# rc-driver-dual-rev-b.net
KiCad netlist of a schematic drawn in EAGLE
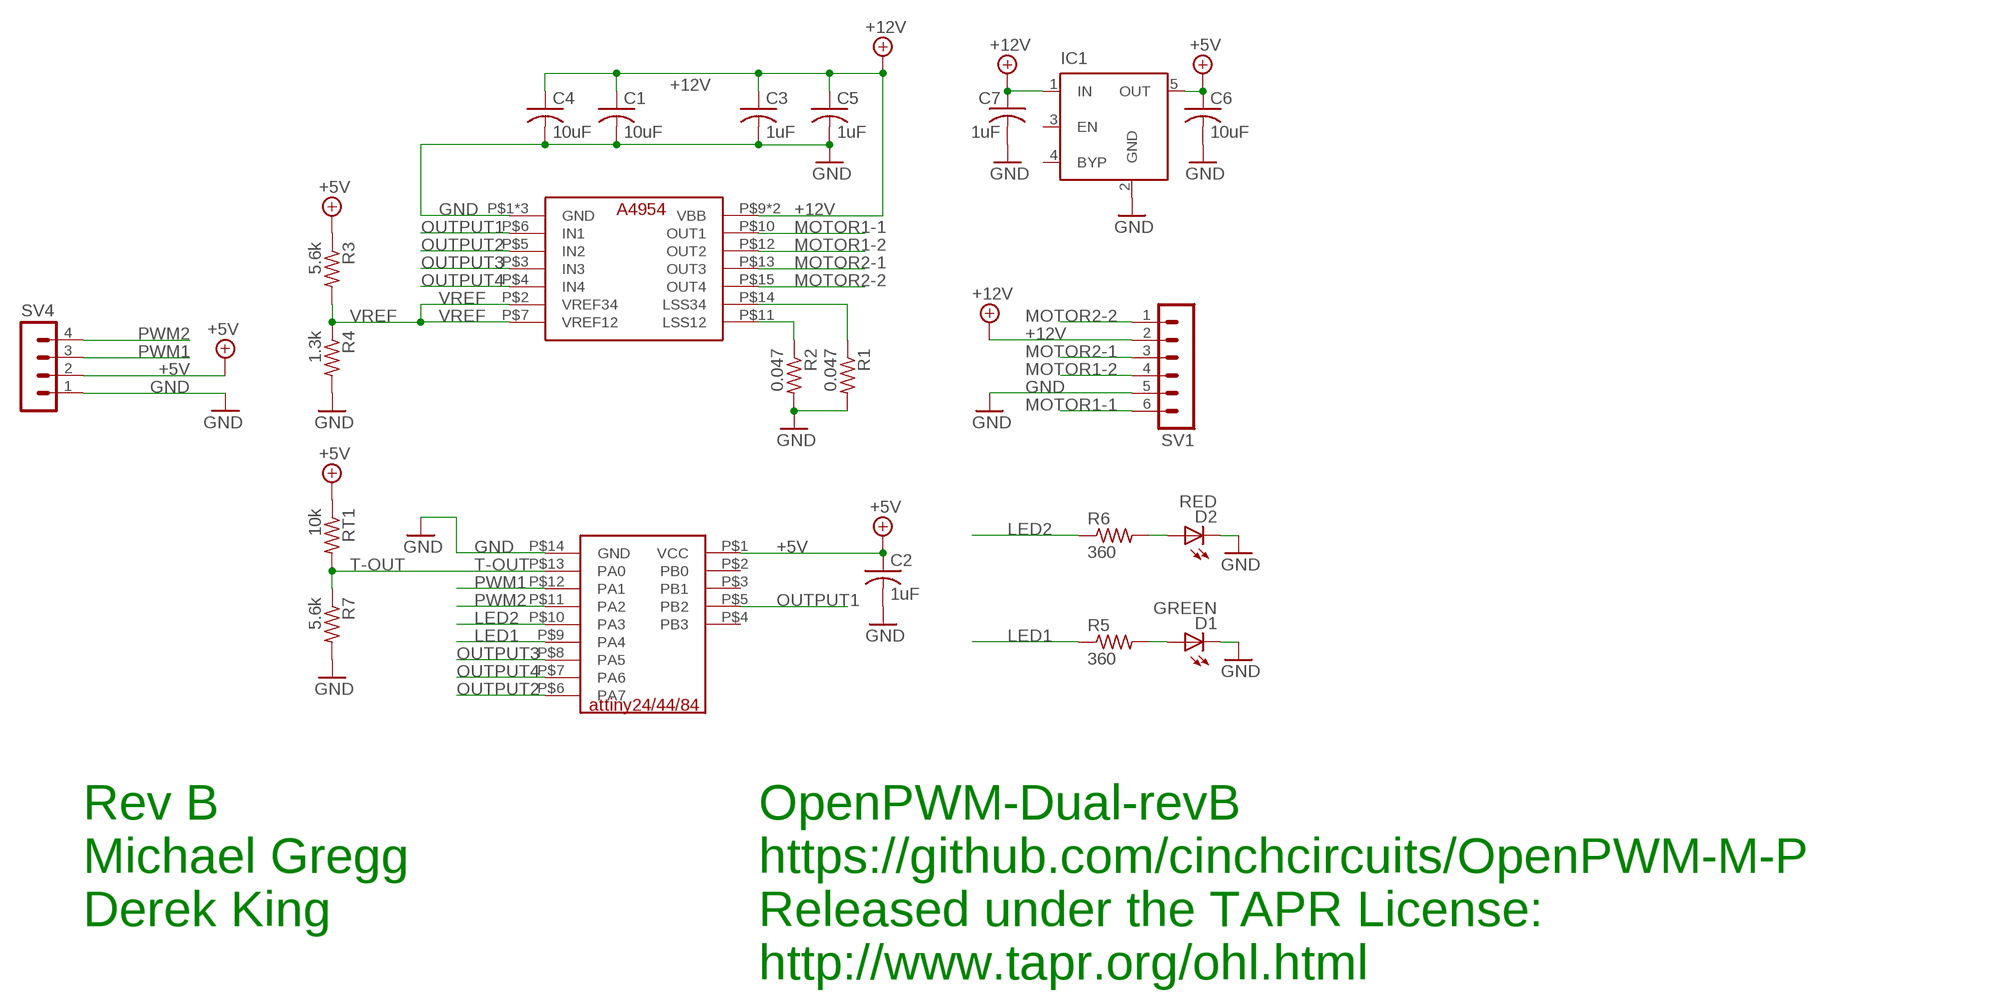
[diagram p0: schematic, sheet 1]

(export (version "E")
  (design (tool "Eeschema 10.0.6"))
  (components
    (comp (ref "C1")
      (value "10uF")
      (footprint "eagle-import:C1206")
      (libsource (lib "eagle-import") (part "C-USC1206"))
    )
    (comp (ref "C2")
      (value "1uF")
      (footprint "eagle-import:C0603")
      (libsource (lib "eagle-import") (part "C-USC0603"))
    )
    (comp (ref "C3")
      (value "1uF")
      (footprint "eagle-import:C0603")
      (libsource (lib "eagle-import") (part "C-USC0603"))
    )
    (comp (ref "C4")
      (value "10uF")
      (footprint "eagle-import:C1206")
      (libsource (lib "eagle-import") (part "C-USC1206"))
    )
    (comp (ref "C5")
      (value "1uF")
      (footprint "eagle-import:C0603")
      (libsource (lib "eagle-import") (part "C-USC0603"))
    )
    (comp (ref "C6")
      (value "10uF")
      (footprint "eagle-import:C1206")
      (libsource (lib "eagle-import") (part "C-USC1206"))
    )
    (comp (ref "C7")
      (value "1uF")
      (footprint "eagle-import:C0603")
      (libsource (lib "eagle-import") (part "C-USC0603"))
    )
    (comp (ref "D1")
      (value "GREEN")
      (footprint "eagle-import:CHIPLED_0603")
      (libsource (lib "eagle-import") (part "LEDCHIPLED_0603"))
    )
    (comp (ref "D2")
      (value "RED")
      (footprint "eagle-import:CHIPLED_0603")
      (libsource (lib "eagle-import") (part "LEDCHIPLED_0603"))
    )
    (comp (ref "IC1")
      (value "MIC5219XX")
      (footprint "eagle-import:SOT23-5")
      (fields (field (name "MF") "Texas Instruments") (field (name "MPN") "TPS70950"))
      (libsource (lib "eagle-import") (part "MIC5219XX"))
    )
    (comp (ref "R1")
      (value "0.047")
      (footprint "eagle-import:R0805")
      (libsource (lib "eagle-import") (part "R-US_R0805"))
    )
    (comp (ref "R2")
      (value "0.047")
      (footprint "eagle-import:R0805")
      (libsource (lib "eagle-import") (part "R-US_R0805"))
    )
    (comp (ref "R3")
      (value "5.6k")
      (footprint "eagle-import:R0603")
      (libsource (lib "eagle-import") (part "R-US_R0603"))
    )
    (comp (ref "R4")
      (value "1.3k")
      (footprint "eagle-import:R0603")
      (libsource (lib "eagle-import") (part "R-US_R0603"))
    )
    (comp (ref "R5")
      (value "360")
      (footprint "eagle-import:R0603")
      (libsource (lib "eagle-import") (part "R-US_R0603"))
    )
    (comp (ref "R6")
      (value "360")
      (footprint "eagle-import:R0603")
      (libsource (lib "eagle-import") (part "R-US_R0603"))
    )
    (comp (ref "R7")
      (value "5.6k")
      (footprint "eagle-import:R0603")
      (libsource (lib "eagle-import") (part "R-US_R0603"))
    )
    (comp (ref "RT1")
      (value "10k")
      (footprint "eagle-import:R0603")
      (libsource (lib "eagle-import") (part "R-US_R0603"))
    )
    (comp (ref "SV1")
      (value "MA06-1")
      (footprint "eagle-import:MA06-1")
      (libsource (lib "eagle-import") (part "MA06-1"))
    )
    (comp (ref "SV4")
      (value "MA04-1")
      (footprint "eagle-import:MA04-1")
      (libsource (lib "eagle-import") (part "MA04-1"))
    )
    (comp (ref "U$1")
      (value "ATTINY24A")
      (footprint "eagle-import:SOIC-14-WIDE")
      (fields (field (name "MF") "Atmel") (field (name "MPN") "ATTINY24A-SSUR"))
      (libsource (lib "eagle-import") (part "ATTINY24A"))
    )
    (comp (ref "U$2")
      (value "A4954-DUAL-HBRIDGE")
      (footprint "eagle-import:TSSOP-16-LP")
      (fields (field (name "MF") "Allegro") (field (name "MPN") "A4954"))
      (libsource (lib "eagle-import") (part "A4954-DUAL-HBRIDGE"))
    )
  )
  (nets
    (net (code "1") (name "+5V") (class "Default")
      (node (ref "C2") (pin "1") (pinfunction "1_1") (pintype "passive"))
      (node (ref "C6") (pin "1") (pinfunction "1_1") (pintype "passive"))
      (node (ref "IC1") (pin "5") (pinfunction "OUT_5") (pintype "output"))
      (node (ref "R3") (pin "1") (pinfunction "1_1") (pintype "passive"))
      (node (ref "RT1") (pin "1") (pinfunction "1_1") (pintype "passive"))
      (node (ref "SV4") (pin "2") (pinfunction "2_2") (pintype "passive"))
      (node (ref "U$1") (pin "P$1") (pinfunction "VCC_P$1") (pintype "bidirectional"))
    )
    (net (code "2") (name "+12V") (class "Default")
      (node (ref "C1") (pin "1") (pinfunction "1_1") (pintype "passive"))
      (node (ref "C3") (pin "1") (pinfunction "1_1") (pintype "passive"))
      (node (ref "C4") (pin "1") (pinfunction "1_1") (pintype "passive"))
      (node (ref "C5") (pin "1") (pinfunction "1_1") (pintype "passive"))
      (node (ref "C7") (pin "1") (pinfunction "1_1") (pintype "passive"))
      (node (ref "IC1") (pin "1") (pinfunction "IN_1") (pintype "input"))
      (node (ref "SV1") (pin "2") (pinfunction "2_2") (pintype "passive"))
      (node (ref "U$2") (pin "P$16") (pinfunction "VBB_P$16") (pintype "bidirectional"))
      (node (ref "U$2") (pin "P$9") (pinfunction "VBB_P$9") (pintype "bidirectional"))
    )
    (net (code "3") (name "/LED1") (class "Default")
      (node (ref "R5") (pin "1") (pinfunction "1_1") (pintype "passive"))
      (node (ref "U$1") (pin "P$9") (pinfunction "PA4_P$9") (pintype "bidirectional"))
    )
    (net (code "4") (name "/LED2") (class "Default")
      (node (ref "R6") (pin "1") (pinfunction "1_1") (pintype "passive"))
      (node (ref "U$1") (pin "P$10") (pinfunction "PA3_P$10") (pintype "bidirectional"))
    )
    (net (code "5") (name "/MOTOR1-1") (class "Default")
      (node (ref "SV1") (pin "6") (pinfunction "6_6") (pintype "passive"))
      (node (ref "U$2") (pin "P$10") (pinfunction "OUT1_P$10") (pintype "bidirectional"))
    )
    (net (code "6") (name "/MOTOR1-2") (class "Default")
      (node (ref "SV1") (pin "4") (pinfunction "4_4") (pintype "passive"))
      (node (ref "U$2") (pin "P$12") (pinfunction "OUT2_P$12") (pintype "bidirectional"))
    )
    (net (code "7") (name "/MOTOR2-1") (class "Default")
      (node (ref "SV1") (pin "3") (pinfunction "3_3") (pintype "passive"))
      (node (ref "U$2") (pin "P$13") (pinfunction "OUT3_P$13") (pintype "bidirectional"))
    )
    (net (code "8") (name "/MOTOR2-2") (class "Default")
      (node (ref "SV1") (pin "1") (pinfunction "1_1") (pintype "passive"))
      (node (ref "U$2") (pin "P$15") (pinfunction "OUT4_P$15") (pintype "bidirectional"))
    )
    (net (code "9") (name "/OUTPUT1") (class "Default")
      (node (ref "U$1") (pin "P$5") (pinfunction "PB2_P$5") (pintype "bidirectional"))
      (node (ref "U$2") (pin "P$6") (pinfunction "IN1_P$6") (pintype "bidirectional"))
    )
    (net (code "10") (name "/OUTPUT2") (class "Default")
      (node (ref "U$1") (pin "P$6") (pinfunction "PA7_P$6") (pintype "bidirectional"))
      (node (ref "U$2") (pin "P$5") (pinfunction "IN2_P$5") (pintype "bidirectional"))
    )
    (net (code "11") (name "/OUTPUT3") (class "Default")
      (node (ref "U$1") (pin "P$8") (pinfunction "PA5_P$8") (pintype "bidirectional"))
      (node (ref "U$2") (pin "P$3") (pinfunction "IN3_P$3") (pintype "bidirectional"))
    )
    (net (code "12") (name "/OUTPUT4") (class "Default")
      (node (ref "U$1") (pin "P$7") (pinfunction "PA6_P$7") (pintype "bidirectional"))
      (node (ref "U$2") (pin "P$4") (pinfunction "IN4_P$4") (pintype "bidirectional"))
    )
    (net (code "13") (name "/PWM1") (class "Default")
      (node (ref "SV4") (pin "3") (pinfunction "3_3") (pintype "passive"))
      (node (ref "U$1") (pin "P$12") (pinfunction "PA1_P$12") (pintype "bidirectional"))
    )
    (net (code "14") (name "/PWM2") (class "Default")
      (node (ref "SV4") (pin "4") (pinfunction "4_4") (pintype "passive"))
      (node (ref "U$1") (pin "P$11") (pinfunction "PA2_P$11") (pintype "bidirectional"))
    )
    (net (code "15") (name "/T-OUT") (class "Default")
      (node (ref "R7") (pin "1") (pinfunction "1_1") (pintype "passive"))
      (node (ref "RT1") (pin "2") (pinfunction "2_2") (pintype "passive"))
      (node (ref "U$1") (pin "P$13") (pinfunction "PA0_P$13") (pintype "bidirectional"))
    )
    (net (code "16") (name "/VREF") (class "Default")
      (node (ref "R3") (pin "2") (pinfunction "2_2") (pintype "passive"))
      (node (ref "R4") (pin "1") (pinfunction "1_1") (pintype "passive"))
      (node (ref "U$2") (pin "P$2") (pinfunction "VREF34_P$2") (pintype "bidirectional"))
      (node (ref "U$2") (pin "P$7") (pinfunction "VREF12_P$7") (pintype "bidirectional"))
    )
    (net (code "17") (name "GND") (class "Default")
      (node (ref "C1") (pin "2") (pinfunction "2_2") (pintype "passive"))
      (node (ref "C2") (pin "2") (pinfunction "2_2") (pintype "passive"))
      (node (ref "C3") (pin "2") (pinfunction "2_2") (pintype "passive"))
      (node (ref "C4") (pin "2") (pinfunction "2_2") (pintype "passive"))
      (node (ref "C5") (pin "2") (pinfunction "2_2") (pintype "passive"))
      (node (ref "C6") (pin "2") (pinfunction "2_2") (pintype "passive"))
      (node (ref "C7") (pin "2") (pinfunction "2_2") (pintype "passive"))
      (node (ref "D1") (pin "C") (pinfunction "C_C") (pintype "passive"))
      (node (ref "D2") (pin "C") (pinfunction "C_C") (pintype "passive"))
      (node (ref "IC1") (pin "2") (pinfunction "GND_2") (pintype "power_in"))
      (node (ref "R1") (pin "2") (pinfunction "2_2") (pintype "passive"))
      (node (ref "R2") (pin "2") (pinfunction "2_2") (pintype "passive"))
      (node (ref "R4") (pin "2") (pinfunction "2_2") (pintype "passive"))
      (node (ref "R7") (pin "2") (pinfunction "2_2") (pintype "passive"))
      (node (ref "SV1") (pin "5") (pinfunction "5_5") (pintype "passive"))
      (node (ref "SV4") (pin "1") (pinfunction "1_1") (pintype "passive"))
      (node (ref "U$1") (pin "P$14") (pinfunction "GND_P$14") (pintype "bidirectional"))
      (node (ref "U$2") (pin "P$1") (pinfunction "GND_P$1") (pintype "bidirectional"))
      (node (ref "U$2") (pin "P$17") (pinfunction "GND_P$17") (pintype "bidirectional"))
      (node (ref "U$2") (pin "P$8") (pinfunction "GND_P$8") (pintype "bidirectional"))
    )
    (net (code "18") (name "Net-(D1-PadA)") (class "Default")
      (node (ref "D1") (pin "A") (pinfunction "A_A") (pintype "passive"))
      (node (ref "R5") (pin "2") (pinfunction "2_2") (pintype "passive"))
    )
    (net (code "19") (name "Net-(D2-PadA)") (class "Default")
      (node (ref "D2") (pin "A") (pinfunction "A_A") (pintype "passive"))
      (node (ref "R6") (pin "2") (pinfunction "2_2") (pintype "passive"))
    )
    (net (code "20") (name "Net-(U$2-LSS12)") (class "Default")
      (node (ref "R2") (pin "1") (pinfunction "1_1") (pintype "passive"))
      (node (ref "U$2") (pin "P$11") (pinfunction "LSS12_P$11") (pintype "bidirectional"))
    )
    (net (code "21") (name "Net-(U$2-LSS34)") (class "Default")
      (node (ref "R1") (pin "1") (pinfunction "1_1") (pintype "passive"))
      (node (ref "U$2") (pin "P$14") (pinfunction "LSS34_P$14") (pintype "bidirectional"))
    )
    (net (code "22") (name "unconnected-(IC1-BYP-Pad4)") (class "Default")
      (node (ref "IC1") (pin "4") (pinfunction "BYP_4") (pintype "passive"))
    )
    (net (code "23") (name "unconnected-(IC1-EN-Pad3)") (class "Default")
      (node (ref "IC1") (pin "3") (pinfunction "EN_3") (pintype "input"))
    )
    (net (code "24") (name "unconnected-(U$1-PB0-PadP$2)") (class "Default")
      (node (ref "U$1") (pin "P$2") (pinfunction "PB0_P$2") (pintype "bidirectional"))
    )
    (net (code "25") (name "unconnected-(U$1-PB1-PadP$3)") (class "Default")
      (node (ref "U$1") (pin "P$3") (pinfunction "PB1_P$3") (pintype "bidirectional"))
    )
    (net (code "26") (name "unconnected-(U$1-PB3-PadP$4)") (class "Default")
      (node (ref "U$1") (pin "P$4") (pinfunction "PB3_P$4") (pintype "bidirectional"))
    )
  )
)
